# Jonathan_ESC.net
KiCad netlist of a schematic drawn in Altium Designer
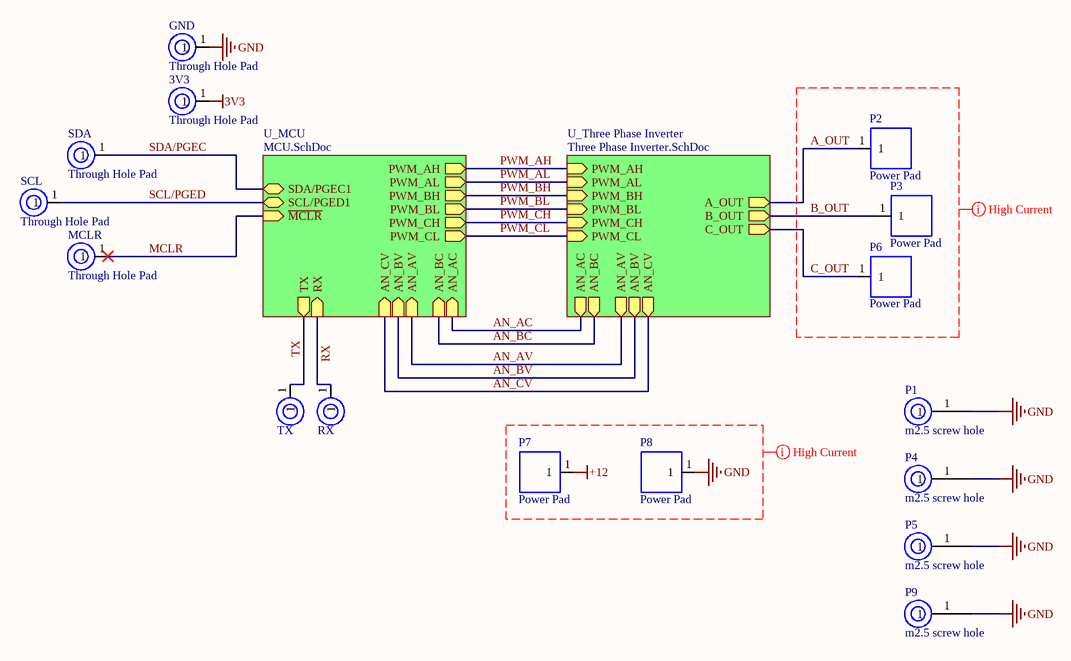
[diagram p0: Jonathan ESC.SchDoc]

(export (version "E")
  (design (tool "Eeschema 10.0.6"))
  (components
    (comp (ref "3V3")
      (value "Through Hole Pad")
      (footprint "THROUGH HOLE PAD")
      (libsource (lib "Schematic Library") (part "Through Hole Pad"))
    )
    (comp (ref "GND")
      (value "Through Hole Pad")
      (footprint "THROUGH HOLE PAD")
      (libsource (lib "Schematic Library") (part "Through Hole Pad"))
    )
    (comp (ref "MCLR")
      (value "Through Hole Pad")
      (footprint "THROUGH HOLE PAD")
      (libsource (lib "Schematic Library") (part "Through Hole Pad"))
    )
    (comp (ref "P1")
      (value "m2.5 screw hole")
      (footprint "m2.5 screw hole")
      (libsource (lib "Schematic Library") (part "m2.5 screw hole"))
    )
    (comp (ref "P2")
      (value "Power Pad")
      (footprint "Power Pad")
      (libsource (lib "Schematic Library") (part "Power Pad"))
    )
    (comp (ref "P3")
      (value "Power Pad")
      (footprint "Power Pad")
      (libsource (lib "Schematic Library") (part "Power Pad"))
    )
    (comp (ref "P4")
      (value "m2.5 screw hole")
      (footprint "m2.5 screw hole")
      (libsource (lib "Schematic Library") (part "m2.5 screw hole"))
    )
    (comp (ref "P5")
      (value "m2.5 screw hole")
      (footprint "m2.5 screw hole")
      (libsource (lib "Schematic Library") (part "m2.5 screw hole"))
    )
    (comp (ref "P6")
      (value "Power Pad")
      (footprint "Power Pad")
      (libsource (lib "Schematic Library") (part "Power Pad"))
    )
    (comp (ref "P7")
      (value "Power Pad")
      (footprint "Power Pad")
      (libsource (lib "Schematic Library") (part "Power Pad"))
    )
    (comp (ref "P8")
      (value "Power Pad")
      (footprint "Power Pad")
      (libsource (lib "Schematic Library") (part "Power Pad"))
    )
    (comp (ref "P9")
      (value "m2.5 screw hole")
      (footprint "m2.5 screw hole")
      (libsource (lib "Schematic Library") (part "m2.5 screw hole"))
    )
    (comp (ref "RX")
      (value "RX")
      (footprint "THROUGH HOLE PAD")
      (libsource (lib "Schematic Library") (part "Through Hole Pad"))
    )
    (comp (ref "SCL")
      (value "Through Hole Pad")
      (footprint "THROUGH HOLE PAD")
      (libsource (lib "Schematic Library") (part "Through Hole Pad"))
    )
    (comp (ref "SDA")
      (value "Through Hole Pad")
      (footprint "THROUGH HOLE PAD")
      (libsource (lib "Schematic Library") (part "Through Hole Pad"))
    )
    (comp (ref "TX")
      (value "TX")
      (footprint "THROUGH HOLE PAD")
      (libsource (lib "Schematic Library") (part "Through Hole Pad"))
    )
  )
  (nets
    (net (code "1") (name "+12") (class "Default")
      (node (ref "P7") (pin "1") (pinfunction "1_1") (pintype "passive"))
    )
    (net (code "7") (name "/A_OUT") (class "Default")
      (node (ref "P2") (pin "1") (pinfunction "1_1") (pintype "passive"))
    )
    (net (code "8") (name "/B_OUT") (class "Default")
      (node (ref "P3") (pin "1") (pinfunction "1_1") (pintype "passive"))
    )
    (net (code "9") (name "/C_OUT") (class "Default")
      (node (ref "P6") (pin "1") (pinfunction "1_1") (pintype "passive"))
    )
    (net (code "10") (name "/MCLR") (class "Default")
      (node (ref "MCLR") (pin "1") (pinfunction "1_1") (pintype "passive+no_connect"))
    )
    (net (code "17") (name "/RX") (class "Default")
      (node (ref "RX") (pin "1") (pinfunction "1_1") (pintype "passive"))
    )
    (net (code "18") (name "/SCL{slash}PGED") (class "Default")
      (node (ref "SCL") (pin "1") (pinfunction "1_1") (pintype "passive"))
    )
    (net (code "19") (name "/SDA{slash}PGEC") (class "Default")
      (node (ref "SDA") (pin "1") (pinfunction "1_1") (pintype "passive"))
    )
    (net (code "20") (name "/TX") (class "Default")
      (node (ref "TX") (pin "1") (pinfunction "1_1") (pintype "passive"))
    )
    (net (code "21") (name "3V3") (class "Default")
      (node (ref "3V3") (pin "1") (pinfunction "1_1") (pintype "passive"))
    )
    (net (code "22") (name "GND") (class "Default")
      (node (ref "GND") (pin "1") (pinfunction "1_1") (pintype "passive"))
      (node (ref "P1") (pin "1") (pinfunction "1_1") (pintype "passive"))
      (node (ref "P4") (pin "1") (pinfunction "1_1") (pintype "passive"))
      (node (ref "P5") (pin "1") (pinfunction "1_1") (pintype "passive"))
      (node (ref "P8") (pin "1") (pinfunction "1_1") (pintype "passive"))
      (node (ref "P9") (pin "1") (pinfunction "1_1") (pintype "passive"))
    )
  )
)
